# Teststand.net
KiCad netlist of a schematic drawn in EAGLE
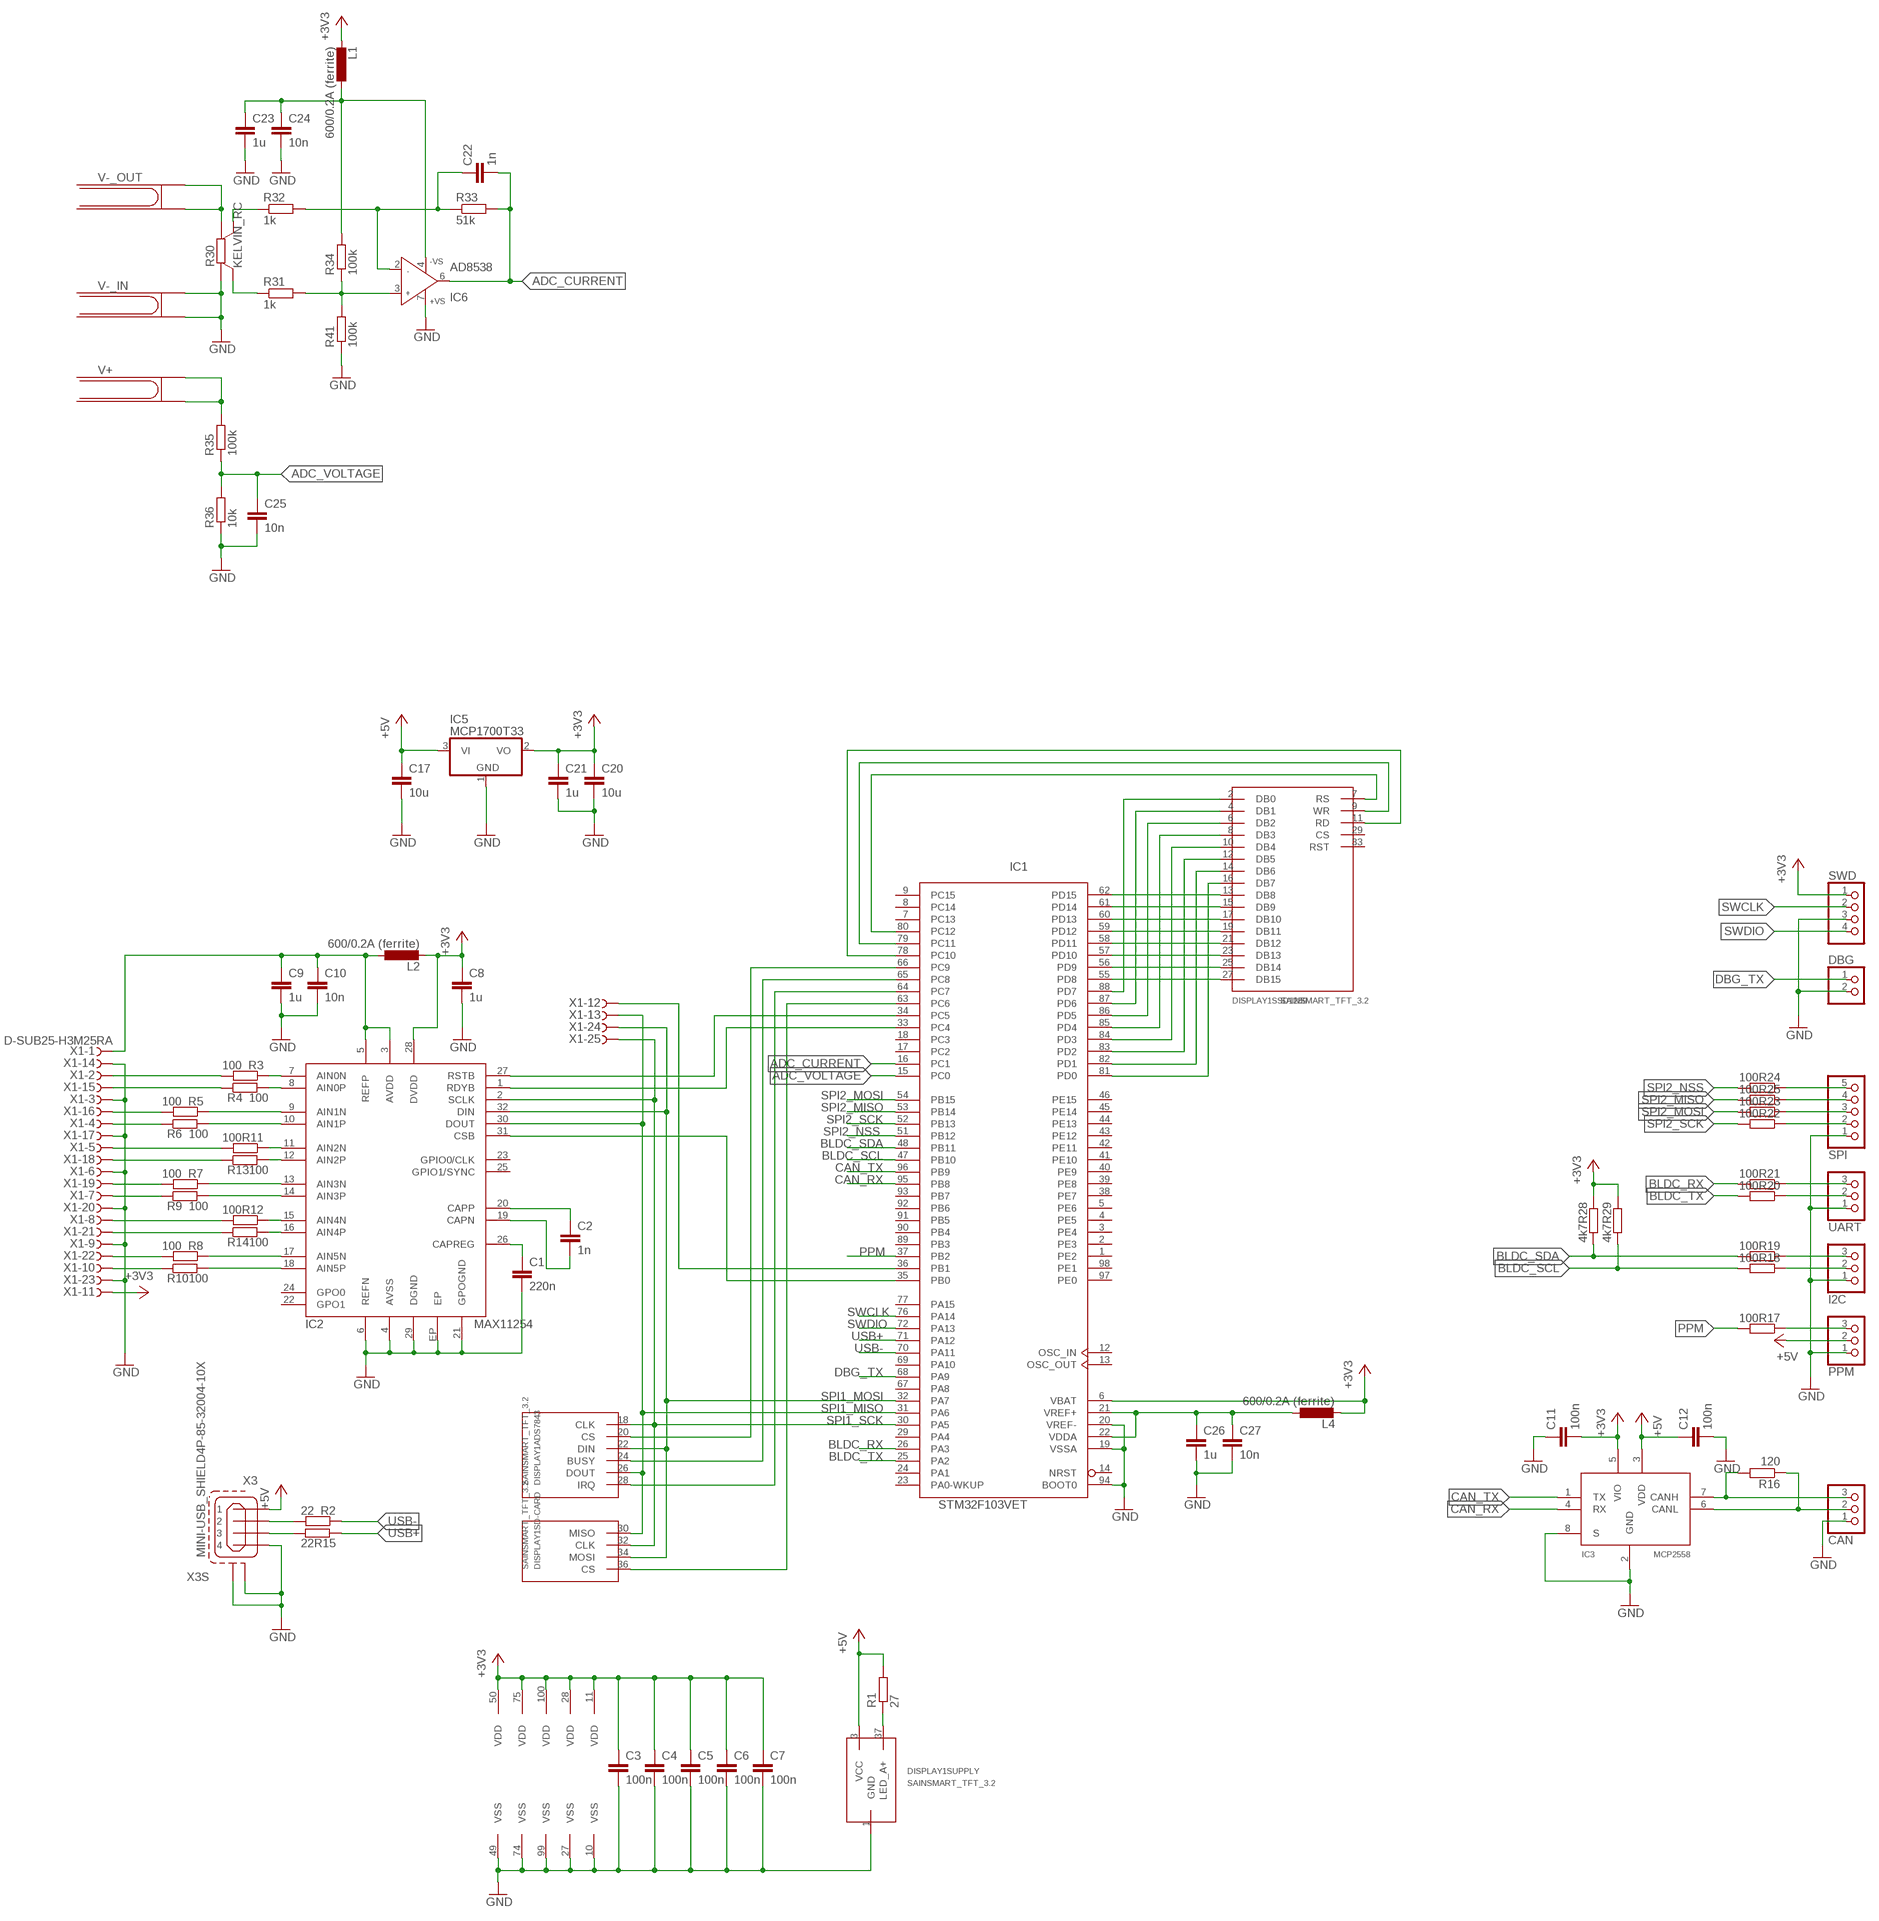
[diagram p0: schematic, sheet 1]

(export (version "E")
  (design (tool "Eeschema 10.0.6"))
  (components
    (comp (ref "C1")
      (value "220n")
      (footprint "eagle-import:C0603K")
      (libsource (lib "eagle-import") (part "C-EUC0603K"))
    )
    (comp (ref "C2")
      (value "1n")
      (footprint "eagle-import:C0603K")
      (libsource (lib "eagle-import") (part "C-EUC0603K"))
    )
    (comp (ref "C3")
      (value "100n")
      (footprint "eagle-import:C0603K")
      (libsource (lib "eagle-import") (part "C-EUC0603K"))
    )
    (comp (ref "C4")
      (value "100n")
      (footprint "eagle-import:C0603K")
      (libsource (lib "eagle-import") (part "C-EUC0603K"))
    )
    (comp (ref "C5")
      (value "100n")
      (footprint "eagle-import:C0603K")
      (libsource (lib "eagle-import") (part "C-EUC0603K"))
    )
    (comp (ref "C6")
      (value "100n")
      (footprint "eagle-import:C0603K")
      (libsource (lib "eagle-import") (part "C-EUC0603K"))
    )
    (comp (ref "C7")
      (value "100n")
      (footprint "eagle-import:C0603K")
      (libsource (lib "eagle-import") (part "C-EUC0603K"))
    )
    (comp (ref "C8")
      (value "1u")
      (footprint "eagle-import:C0603K")
      (libsource (lib "eagle-import") (part "C-EUC0603K"))
    )
    (comp (ref "C9")
      (value "1u")
      (footprint "eagle-import:C0603K")
      (libsource (lib "eagle-import") (part "C-EUC0603K"))
    )
    (comp (ref "C10")
      (value "10n")
      (footprint "eagle-import:C0603K")
      (libsource (lib "eagle-import") (part "C-EUC0603K"))
    )
    (comp (ref "C11")
      (value "100n")
      (footprint "eagle-import:C0603K")
      (libsource (lib "eagle-import") (part "C-EUC0603K"))
    )
    (comp (ref "C12")
      (value "100n")
      (footprint "eagle-import:C0603K")
      (libsource (lib "eagle-import") (part "C-EUC0603K"))
    )
    (comp (ref "C17")
      (value "10u")
      (footprint "eagle-import:C1206")
      (libsource (lib "eagle-import") (part "C-EUC1206"))
    )
    (comp (ref "C20")
      (value "10u")
      (footprint "eagle-import:C1206")
      (libsource (lib "eagle-import") (part "C-EUC1206"))
    )
    (comp (ref "C21")
      (value "1u")
      (footprint "eagle-import:C1206")
      (libsource (lib "eagle-import") (part "C-EUC1206"))
    )
    (comp (ref "C22")
      (value "1n")
      (footprint "eagle-import:C0603K")
      (libsource (lib "eagle-import") (part "C-EUC0603K"))
    )
    (comp (ref "C23")
      (value "1u")
      (footprint "eagle-import:C0603K")
      (libsource (lib "eagle-import") (part "C-EUC0603K"))
    )
    (comp (ref "C24")
      (value "10n")
      (footprint "eagle-import:C0603K")
      (libsource (lib "eagle-import") (part "C-EUC0603K"))
    )
    (comp (ref "C25")
      (value "10n")
      (footprint "eagle-import:C0603K")
      (libsource (lib "eagle-import") (part "C-EUC0603K"))
    )
    (comp (ref "C26")
      (value "1u")
      (footprint "eagle-import:C0603K")
      (libsource (lib "eagle-import") (part "C-EUC0603K"))
    )
    (comp (ref "C27")
      (value "10n")
      (footprint "eagle-import:C0603K")
      (libsource (lib "eagle-import") (part "C-EUC0603K"))
    )
    (comp (ref "CAN")
      (value "PINHD-1X3/90")
      (footprint "eagle-import:1X03_90")
      (libsource (lib "eagle-import") (part "PINHD-1X3/90"))
    )
    (comp (ref "DBG")
      (value "PINHD-1X2")
      (footprint "eagle-import:1X02")
      (libsource (lib "eagle-import") (part "PINHD-1X2"))
    )
    (comp (ref "DISPLAY1")
      (value "SAINSMART_TFT_3.2")
      (footprint "eagle-import:SAINSMART_TFT_3.2")
      (libsource (lib "eagle-import") (part "SAINSMART_TFT_3.2"))
    )
    (comp (ref "I2C")
      (value "PINHD-1X3/90")
      (footprint "eagle-import:1X03_90")
      (libsource (lib "eagle-import") (part "PINHD-1X3/90"))
    )
    (comp (ref "IC1")
      (value "STM32F103VET")
      (footprint "eagle-import:LQFP100")
      (libsource (lib "eagle-import") (part "STM32F103VTE"))
    )
    (comp (ref "IC2")
      (value "MAX11254")
      (footprint "eagle-import:TQFP32-EP")
      (libsource (lib "eagle-import") (part "MAX11254"))
    )
    (comp (ref "IC3")
      (value "MCP2558")
      (footprint "eagle-import:SOIC8")
      (libsource (lib "eagle-import") (part "MCP2558"))
    )
    (comp (ref "IC5")
      (value "MCP1700T33")
      (footprint "eagle-import:SOT23")
      (libsource (lib "eagle-import") (part "MCP1703CB"))
    )
    (comp (ref "IC6")
      (value "AD8538")
      (footprint "eagle-import:SO8")
      (fields (field (name "MPN") "AD8519ARZ"))
      (libsource (lib "eagle-import") (part "AD8519R"))
    )
    (comp (ref "L1")
      (value "600/0.2A (ferrite)")
      (footprint "eagle-import:L2012C")
      (libsource (lib "eagle-import") (part "L-EUL2012C"))
    )
    (comp (ref "L2")
      (value "600/0.2A (ferrite)")
      (footprint "eagle-import:L2012C")
      (libsource (lib "eagle-import") (part "L-EUL2012C"))
    )
    (comp (ref "L4")
      (value "600/0.2A (ferrite)")
      (footprint "eagle-import:L2012C")
      (libsource (lib "eagle-import") (part "L-EUL2012C"))
    )
    (comp (ref "PPM")
      (value "PINHD-1X3/90")
      (footprint "eagle-import:1X03_90")
      (libsource (lib "eagle-import") (part "PINHD-1X3/90"))
    )
    (comp (ref "R1")
      (value "27")
      (footprint "eagle-import:M1206")
      (libsource (lib "eagle-import") (part "R-EU_M1206"))
    )
    (comp (ref "R2")
      (value "22")
      (footprint "eagle-import:R0603")
      (libsource (lib "eagle-import") (part "R-EU_R0603"))
    )
    (comp (ref "R3")
      (value "100")
      (footprint "eagle-import:R0603")
      (libsource (lib "eagle-import") (part "R-EU_R0603"))
    )
    (comp (ref "R4")
      (value "100")
      (footprint "eagle-import:R0603")
      (libsource (lib "eagle-import") (part "R-EU_R0603"))
    )
    (comp (ref "R5")
      (value "100")
      (footprint "eagle-import:R0603")
      (libsource (lib "eagle-import") (part "R-EU_R0603"))
    )
    (comp (ref "R6")
      (value "100")
      (footprint "eagle-import:R0603")
      (libsource (lib "eagle-import") (part "R-EU_R0603"))
    )
    (comp (ref "R7")
      (value "100")
      (footprint "eagle-import:R0603")
      (libsource (lib "eagle-import") (part "R-EU_R0603"))
    )
    (comp (ref "R8")
      (value "100")
      (footprint "eagle-import:R0603")
      (libsource (lib "eagle-import") (part "R-EU_R0603"))
    )
    (comp (ref "R9")
      (value "100")
      (footprint "eagle-import:R0603")
      (libsource (lib "eagle-import") (part "R-EU_R0603"))
    )
    (comp (ref "R10")
      (value "100")
      (footprint "eagle-import:R0603")
      (libsource (lib "eagle-import") (part "R-EU_R0603"))
    )
    (comp (ref "R11")
      (value "100")
      (footprint "eagle-import:R0603")
      (libsource (lib "eagle-import") (part "R-EU_R0603"))
    )
    (comp (ref "R12")
      (value "100")
      (footprint "eagle-import:R0603")
      (libsource (lib "eagle-import") (part "R-EU_R0603"))
    )
    (comp (ref "R13")
      (value "100")
      (footprint "eagle-import:R0603")
      (libsource (lib "eagle-import") (part "R-EU_R0603"))
    )
    (comp (ref "R14")
      (value "100")
      (footprint "eagle-import:R0603")
      (libsource (lib "eagle-import") (part "R-EU_R0603"))
    )
    (comp (ref "R15")
      (value "22")
      (footprint "eagle-import:R0603")
      (libsource (lib "eagle-import") (part "R-EU_R0603"))
    )
    (comp (ref "R16")
      (value "120")
      (footprint "eagle-import:R0603")
      (libsource (lib "eagle-import") (part "R-EU_R0603"))
    )
    (comp (ref "R17")
      (value "100")
      (footprint "eagle-import:R0603")
      (libsource (lib "eagle-import") (part "R-EU_R0603"))
    )
    (comp (ref "R18")
      (value "100")
      (footprint "eagle-import:R0603")
      (libsource (lib "eagle-import") (part "R-EU_R0603"))
    )
    (comp (ref "R19")
      (value "100")
      (footprint "eagle-import:R0603")
      (libsource (lib "eagle-import") (part "R-EU_R0603"))
    )
    (comp (ref "R20")
      (value "100")
      (footprint "eagle-import:R0603")
      (libsource (lib "eagle-import") (part "R-EU_R0603"))
    )
    (comp (ref "R21")
      (value "100")
      (footprint "eagle-import:R0603")
      (libsource (lib "eagle-import") (part "R-EU_R0603"))
    )
    (comp (ref "R22")
      (value "100")
      (footprint "eagle-import:R0603")
      (libsource (lib "eagle-import") (part "R-EU_R0603"))
    )
    (comp (ref "R23")
      (value "100")
      (footprint "eagle-import:R0603")
      (libsource (lib "eagle-import") (part "R-EU_R0603"))
    )
    (comp (ref "R24")
      (value "100")
      (footprint "eagle-import:R0603")
      (libsource (lib "eagle-import") (part "R-EU_R0603"))
    )
    (comp (ref "R25")
      (value "100")
      (footprint "eagle-import:R0603")
      (libsource (lib "eagle-import") (part "R-EU_R0603"))
    )
    (comp (ref "R28")
      (value "4k7")
      (footprint "eagle-import:R0603")
      (libsource (lib "eagle-import") (part "R-EU_R0603"))
    )
    (comp (ref "R29")
      (value "4k7")
      (footprint "eagle-import:R0603")
      (libsource (lib "eagle-import") (part "R-EU_R0603"))
    )
    (comp (ref "R30")
      (value "KELVIN_RC")
      (footprint "eagle-import:CST0612")
      (libsource (lib "eagle-import") (part "KELVIN_RC"))
    )
    (comp (ref "R31")
      (value "1k")
      (footprint "eagle-import:R0603")
      (libsource (lib "eagle-import") (part "R-EU_R0603"))
    )
    (comp (ref "R32")
      (value "1k")
      (footprint "eagle-import:R0603")
      (libsource (lib "eagle-import") (part "R-EU_R0603"))
    )
    (comp (ref "R33")
      (value "51k")
      (footprint "eagle-import:R0603")
      (libsource (lib "eagle-import") (part "R-EU_R0603"))
    )
    (comp (ref "R34")
      (value "100k")
      (footprint "eagle-import:R0603")
      (libsource (lib "eagle-import") (part "R-EU_R0603"))
    )
    (comp (ref "R35")
      (value "100k")
      (footprint "eagle-import:R0603")
      (libsource (lib "eagle-import") (part "R-EU_R0603"))
    )
    (comp (ref "R36")
      (value "10k")
      (footprint "eagle-import:R0603")
      (libsource (lib "eagle-import") (part "R-EU_R0603"))
    )
    (comp (ref "R41")
      (value "100k")
      (footprint "eagle-import:R0603")
      (libsource (lib "eagle-import") (part "R-EU_R0603"))
    )
    (comp (ref "SPI")
      (value "PINHD-1X5/90")
      (footprint "eagle-import:1X05_90")
      (libsource (lib "eagle-import") (part "PINHD-1X5/90"))
    )
    (comp (ref "SWD")
      (value "PINHD-1X4")
      (footprint "eagle-import:1X04")
      (libsource (lib "eagle-import") (part "PINHD-1X4"))
    )
    (comp (ref "UART")
      (value "PINHD-1X3/90")
      (footprint "eagle-import:1X03_90")
      (libsource (lib "eagle-import") (part "PINHD-1X3/90"))
    )
    (comp (ref "V+")
      (value "4MMJACK")
      (footprint "eagle-import:4MMJACK")
      (libsource (lib "eagle-import") (part "4MMJACK"))
    )
    (comp (ref "V-_IN")
      (value "4MMJACK")
      (footprint "eagle-import:4MMJACK")
      (libsource (lib "eagle-import") (part "4MMJACK"))
    )
    (comp (ref "V-_OUT")
      (value "4MMJACK")
      (footprint "eagle-import:4MMJACK")
      (libsource (lib "eagle-import") (part "4MMJACK"))
    )
    (comp (ref "X1")
      (value "D-SUB25-H3M25RA")
      (footprint "eagle-import:H3M25RA")
      (libsource (lib "eagle-import") (part "D-SUB25-H3M25RA"))
    )
    (comp (ref "X3")
      (value "MINI-USB_SHIELD4P-85-32004-10X")
      (footprint "eagle-import:85-32004-10X")
      (libsource (lib "eagle-import") (part "MINI-USB_SHIELD4P-85-32004-10X"))
    )
  )
  (nets
    (net (code "1") (name "+3V3") (class "Default")
      (node (ref "C11") (pin "2") (pinfunction "2_2") (pintype "passive"))
      (node (ref "C20") (pin "1") (pinfunction "1_1") (pintype "passive"))
      (node (ref "C21") (pin "1") (pinfunction "1_1") (pintype "passive"))
      (node (ref "C3") (pin "1") (pinfunction "1_1") (pintype "passive"))
      (node (ref "C4") (pin "1") (pinfunction "1_1") (pintype "passive"))
      (node (ref "C5") (pin "1") (pinfunction "1_1") (pintype "passive"))
      (node (ref "C6") (pin "1") (pinfunction "1_1") (pintype "passive"))
      (node (ref "C7") (pin "1") (pinfunction "1_1") (pintype "passive"))
      (node (ref "C8") (pin "1") (pinfunction "1_1") (pintype "passive"))
      (node (ref "IC1") (pin "100") (pinfunction "VDD_100") (pintype "power_in"))
      (node (ref "IC1") (pin "11") (pinfunction "VDD_11") (pintype "power_in"))
      (node (ref "IC1") (pin "28") (pinfunction "VDD_28") (pintype "power_in"))
      (node (ref "IC1") (pin "50") (pinfunction "VDD_50") (pintype "power_in"))
      (node (ref "IC1") (pin "6") (pinfunction "VBAT_6") (pintype "power_in"))
      (node (ref "IC1") (pin "75") (pinfunction "VDD_75") (pintype "power_in"))
      (node (ref "IC2") (pin "28") (pinfunction "DVDD_28") (pintype "bidirectional"))
      (node (ref "IC3") (pin "5") (pinfunction "VIO_5") (pintype "bidirectional"))
      (node (ref "IC5") (pin "2") (pinfunction "VO_2") (pintype "passive"))
      (node (ref "L1") (pin "2") (pinfunction "2_2") (pintype "passive"))
      (node (ref "L2") (pin "2") (pinfunction "2_2") (pintype "passive"))
      (node (ref "L4") (pin "2") (pinfunction "2_2") (pintype "passive"))
      (node (ref "R28") (pin "1") (pinfunction "1_1") (pintype "passive"))
      (node (ref "R29") (pin "1") (pinfunction "1_1") (pintype "passive"))
      (node (ref "SWD") (pin "1") (pinfunction "1_1") (pintype "passive"))
      (node (ref "X1") (pin "11") (pinfunction "F_11") (pintype "passive"))
    )
    (net (code "2") (name "+5V") (class "Default")
      (node (ref "C12") (pin "1") (pinfunction "1_1") (pintype "passive"))
      (node (ref "C17") (pin "1") (pinfunction "1_1") (pintype "passive"))
      (node (ref "DISPLAY1") (pin "3") (pinfunction "VCC_3") (pintype "bidirectional"))
      (node (ref "IC3") (pin "3") (pinfunction "VDD_3") (pintype "bidirectional"))
      (node (ref "IC5") (pin "3") (pinfunction "VI_3") (pintype "input"))
      (node (ref "PPM") (pin "2") (pinfunction "2_2") (pintype "passive"))
      (node (ref "R1") (pin "2") (pinfunction "2_2") (pintype "passive"))
      (node (ref "X3") (pin "1") (pinfunction "1_1") (pintype "passive"))
    )
    (net (code "3") (name "/SPI1_MISO") (class "Default")
      (node (ref "DISPLAY1") (pin "26") (pinfunction "DOUT_26") (pintype "bidirectional"))
      (node (ref "DISPLAY1") (pin "30") (pinfunction "MISO_30") (pintype "bidirectional"))
      (node (ref "IC1") (pin "31") (pinfunction "PA6_31") (pintype "bidirectional"))
      (node (ref "IC2") (pin "30") (pinfunction "DOUT_30") (pintype "bidirectional"))
      (node (ref "X1") (pin "13") (pinfunction "F_13") (pintype "passive"))
    )
    (net (code "4") (name "/SPI1_MOSI") (class "Default")
      (node (ref "DISPLAY1") (pin "22") (pinfunction "DIN_22") (pintype "bidirectional"))
      (node (ref "DISPLAY1") (pin "34") (pinfunction "MOSI_34") (pintype "bidirectional"))
      (node (ref "IC1") (pin "32") (pinfunction "PA7_32") (pintype "bidirectional"))
      (node (ref "IC2") (pin "32") (pinfunction "DIN_32") (pintype "bidirectional"))
      (node (ref "X1") (pin "24") (pinfunction "F_24") (pintype "passive"))
    )
    (net (code "5") (name "/SPI1_SCK") (class "Default")
      (node (ref "DISPLAY1") (pin "18") (pinfunction "CLK_18") (pintype "bidirectional"))
      (node (ref "DISPLAY1") (pin "32") (pinfunction "CLK_32") (pintype "bidirectional"))
      (node (ref "IC1") (pin "30") (pinfunction "PA5_30") (pintype "bidirectional"))
      (node (ref "IC2") (pin "2") (pinfunction "SCLK_2") (pintype "bidirectional"))
      (node (ref "X1") (pin "25") (pinfunction "F_25") (pintype "passive"))
    )
    (net (code "6") (name "ADC_CURRENT") (class "Default")
      (node (ref "C22") (pin "2") (pinfunction "2_2") (pintype "passive"))
      (node (ref "IC1") (pin "16") (pinfunction "PC1_16") (pintype "bidirectional"))
      (node (ref "IC6") (pin "6") (pinfunction "OUT_6") (pintype "output"))
      (node (ref "R33") (pin "2") (pinfunction "2_2") (pintype "passive"))
    )
    (net (code "7") (name "ADC_VOLTAGE") (class "Default")
      (node (ref "C25") (pin "1") (pinfunction "1_1") (pintype "passive"))
      (node (ref "IC1") (pin "15") (pinfunction "PC0_15") (pintype "bidirectional"))
      (node (ref "R35") (pin "1") (pinfunction "1_1") (pintype "passive"))
      (node (ref "R36") (pin "2") (pinfunction "2_2") (pintype "passive"))
    )
    (net (code "8") (name "BLDC_RX") (class "Default")
      (node (ref "IC1") (pin "26") (pinfunction "PA3_26") (pintype "bidirectional"))
      (node (ref "R21") (pin "2") (pinfunction "2_2") (pintype "passive"))
    )
    (net (code "9") (name "BLDC_SCL") (class "Default")
      (node (ref "IC1") (pin "47") (pinfunction "PB10_47") (pintype "bidirectional"))
      (node (ref "R18") (pin "2") (pinfunction "2_2") (pintype "passive"))
      (node (ref "R29") (pin "2") (pinfunction "2_2") (pintype "passive"))
    )
    (net (code "10") (name "BLDC_SDA") (class "Default")
      (node (ref "IC1") (pin "48") (pinfunction "PB11_48") (pintype "bidirectional"))
      (node (ref "R19") (pin "2") (pinfunction "2_2") (pintype "passive"))
      (node (ref "R28") (pin "2") (pinfunction "2_2") (pintype "passive"))
    )
    (net (code "11") (name "BLDC_TX") (class "Default")
      (node (ref "IC1") (pin "25") (pinfunction "PA2_25") (pintype "bidirectional"))
      (node (ref "R20") (pin "2") (pinfunction "2_2") (pintype "passive"))
    )
    (net (code "12") (name "CAN_RX") (class "Default")
      (node (ref "IC1") (pin "95") (pinfunction "PB8_95") (pintype "bidirectional"))
      (node (ref "IC3") (pin "4") (pinfunction "RX_4") (pintype "bidirectional"))
    )
    (net (code "13") (name "CAN_TX") (class "Default")
      (node (ref "IC1") (pin "96") (pinfunction "PB9_96") (pintype "bidirectional"))
      (node (ref "IC3") (pin "1") (pinfunction "TX_1") (pintype "bidirectional"))
    )
    (net (code "14") (name "DBG_TX") (class "Default")
      (node (ref "DBG") (pin "1") (pinfunction "1_1") (pintype "passive"))
      (node (ref "IC1") (pin "68") (pinfunction "PA9_68") (pintype "bidirectional"))
    )
    (net (code "15") (name "GND") (class "Default")
      (node (ref "C1") (pin "2") (pinfunction "2_2") (pintype "passive"))
      (node (ref "C10") (pin "2") (pinfunction "2_2") (pintype "passive"))
      (node (ref "C11") (pin "1") (pinfunction "1_1") (pintype "passive"))
      (node (ref "C12") (pin "2") (pinfunction "2_2") (pintype "passive"))
      (node (ref "C17") (pin "2") (pinfunction "2_2") (pintype "passive"))
      (node (ref "C20") (pin "2") (pinfunction "2_2") (pintype "passive"))
      (node (ref "C21") (pin "2") (pinfunction "2_2") (pintype "passive"))
      (node (ref "C23") (pin "2") (pinfunction "2_2") (pintype "passive"))
      (node (ref "C24") (pin "2") (pinfunction "2_2") (pintype "passive"))
      (node (ref "C25") (pin "2") (pinfunction "2_2") (pintype "passive"))
      (node (ref "C26") (pin "2") (pinfunction "2_2") (pintype "passive"))
      (node (ref "C27") (pin "2") (pinfunction "2_2") (pintype "passive"))
      (node (ref "C3") (pin "2") (pinfunction "2_2") (pintype "passive"))
      (node (ref "C4") (pin "2") (pinfunction "2_2") (pintype "passive"))
      (node (ref "C5") (pin "2") (pinfunction "2_2") (pintype "passive"))
      (node (ref "C6") (pin "2") (pinfunction "2_2") (pintype "passive"))
      (node (ref "C7") (pin "2") (pinfunction "2_2") (pintype "passive"))
      (node (ref "C8") (pin "2") (pinfunction "2_2") (pintype "passive"))
      (node (ref "C9") (pin "2") (pinfunction "2_2") (pintype "passive"))
      (node (ref "CAN") (pin "1") (pinfunction "1_1") (pintype "passive"))
      (node (ref "DBG") (pin "2") (pinfunction "2_2") (pintype "passive"))
      (node (ref "DISPLAY1") (pin "1") (pinfunction "GND_1") (pintype "bidirectional"))
      (node (ref "I2C") (pin "1") (pinfunction "1_1") (pintype "passive"))
      (node (ref "IC1") (pin "10") (pinfunction "VSS_10") (pintype "power_in"))
      (node (ref "IC1") (pin "19") (pinfunction "VSSA_19") (pintype "power_in"))
      (node (ref "IC1") (pin "20") (pinfunction "VREF-_20") (pintype "power_in"))
      (node (ref "IC1") (pin "27") (pinfunction "VSS_27") (pintype "power_in"))
      (node (ref "IC1") (pin "49") (pinfunction "VSS_49") (pintype "power_in"))
      (node (ref "IC1") (pin "74") (pinfunction "VSS_74") (pintype "power_in"))
      (node (ref "IC1") (pin "94") (pinfunction "BOOT0_94") (pintype "input"))
      (node (ref "IC1") (pin "99") (pinfunction "VSS_99") (pintype "power_in"))
      (node (ref "IC2") (pin "21") (pinfunction "GPOGND_21") (pintype "bidirectional"))
      (node (ref "IC2") (pin "29") (pinfunction "DGND_29") (pintype "bidirectional"))
      (node (ref "IC2") (pin "4") (pinfunction "AVSS_4") (pintype "bidirectional"))
      (node (ref "IC2") (pin "6") (pinfunction "REFN_6") (pintype "bidirectional"))
      (node (ref "IC2") (pin "EP") (pinfunction "EP_EP") (pintype "bidirectional"))
      (node (ref "IC3") (pin "2") (pinfunction "GND_2") (pintype "bidirectional"))
      (node (ref "IC3") (pin "8") (pinfunction "S_8") (pintype "bidirectional"))
      (node (ref "IC5") (pin "1") (pinfunction "GND_1") (pintype "passive"))
      (node (ref "IC6") (pin "7") (pinfunction "+VS_7") (pintype "input"))
      (node (ref "PPM") (pin "1") (pinfunction "1_1") (pintype "passive"))
      (node (ref "R30") (pin "B") (pinfunction "B_B") (pintype "passive"))
      (node (ref "R36") (pin "1") (pinfunction "1_1") (pintype "passive"))
      (node (ref "R41") (pin "1") (pinfunction "1_1") (pintype "passive"))
      (node (ref "SPI") (pin "1") (pinfunction "1_1") (pintype "passive"))
      (node (ref "SWD") (pin "3") (pinfunction "3_3") (pintype "passive"))
      (node (ref "UART") (pin "1") (pinfunction "1_1") (pintype "passive"))
      (node (ref "V-_IN") (pin "1@1") (pinfunction "1_1@1") (pintype "bidirectional"))
      (node (ref "V-_IN") (pin "1@2") (pinfunction "2_1@2") (pintype "bidirectional"))
      (node (ref "X1") (pin "14") (pinfunction "F_14") (pintype "passive"))
      (node (ref "X1") (pin "17") (pinfunction "F_17") (pintype "passive"))
      (node (ref "X1") (pin "20") (pinfunction "F_20") (pintype "passive"))
      (node (ref "X1") (pin "23") (pinfunction "F_23") (pintype "passive"))
      (node (ref "X1") (pin "3") (pinfunction "F_3") (pintype "passive"))
      (node (ref "X1") (pin "6") (pinfunction "F_6") (pintype "passive"))
      (node (ref "X1") (pin "9") (pinfunction "F_9") (pintype "passive"))
      (node (ref "X3") (pin "4") (pinfunction "4_4") (pintype "passive"))
      (node (ref "X3") (pin "M1") (pinfunction "S1_M1") (pintype "passive"))
      (node (ref "X3") (pin "M2") (pinfunction "S2_M2") (pintype "passive"))
    )
    (net (code "16") (name "Net-(DISPLAY1A-BUSY)") (class "Default")
      (node (ref "DISPLAY1") (pin "24") (pinfunction "BUSY_24") (pintype "bidirectional"))
      (node (ref "IC1") (pin "65") (pinfunction "PC8_65") (pintype "bidirectional"))
    )
    (net (code "17") (name "Net-(DISPLAY1A-CS)") (class "Default")
      (node (ref "DISPLAY1") (pin "20") (pinfunction "CS_20") (pintype "bidirectional"))
      (node (ref "IC1") (pin "66") (pinfunction "PC9_66") (pintype "bidirectional"))
    )
    (net (code "18") (name "Net-(DISPLAY1A-IRQ)") (class "Default")
      (node (ref "DISPLAY1") (pin "28") (pinfunction "IRQ_28") (pintype "bidirectional"))
      (node (ref "IC1") (pin "64") (pinfunction "PC7_64") (pintype "bidirectional"))
    )
    (net (code "19") (name "Net-(DISPLAY1B-CS)") (class "Default")
      (node (ref "DISPLAY1") (pin "36") (pinfunction "CS_36") (pintype "bidirectional"))
      (node (ref "IC1") (pin "63") (pinfunction "PC6_63") (pintype "bidirectional"))
    )
    (net (code "20") (name "Net-(DISPLAY1C-DB0)") (class "Default")
      (node (ref "DISPLAY1") (pin "2") (pinfunction "DB0_2") (pintype "bidirectional"))
      (node (ref "IC1") (pin "88") (pinfunction "PD7_88") (pintype "bidirectional"))
    )
    (net (code "21") (name "Net-(DISPLAY1C-DB1)") (class "Default")
      (node (ref "DISPLAY1") (pin "4") (pinfunction "DB1_4") (pintype "bidirectional"))
      (node (ref "IC1") (pin "87") (pinfunction "PD6_87") (pintype "bidirectional"))
    )
    (net (code "22") (name "Net-(DISPLAY1C-DB2)") (class "Default")
      (node (ref "DISPLAY1") (pin "6") (pinfunction "DB2_6") (pintype "bidirectional"))
      (node (ref "IC1") (pin "86") (pinfunction "PD5_86") (pintype "bidirectional"))
    )
    (net (code "23") (name "Net-(DISPLAY1C-DB3)") (class "Default")
      (node (ref "DISPLAY1") (pin "8") (pinfunction "DB3_8") (pintype "bidirectional"))
      (node (ref "IC1") (pin "85") (pinfunction "PD4_85") (pintype "bidirectional"))
    )
    (net (code "24") (name "Net-(DISPLAY1C-DB4)") (class "Default")
      (node (ref "DISPLAY1") (pin "10") (pinfunction "DB4_10") (pintype "bidirectional"))
      (node (ref "IC1") (pin "84") (pinfunction "PD3_84") (pintype "bidirectional"))
    )
    (net (code "25") (name "Net-(DISPLAY1C-DB5)") (class "Default")
      (node (ref "DISPLAY1") (pin "12") (pinfunction "DB5_12") (pintype "bidirectional"))
      (node (ref "IC1") (pin "83") (pinfunction "PD2_83") (pintype "bidirectional"))
    )
    (net (code "26") (name "Net-(DISPLAY1C-DB6)") (class "Default")
      (node (ref "DISPLAY1") (pin "14") (pinfunction "DB6_14") (pintype "bidirectional"))
      (node (ref "IC1") (pin "82") (pinfunction "PD1_82") (pintype "bidirectional"))
    )
    (net (code "27") (name "Net-(DISPLAY1C-DB7)") (class "Default")
      (node (ref "DISPLAY1") (pin "16") (pinfunction "DB7_16") (pintype "bidirectional"))
      (node (ref "IC1") (pin "81") (pinfunction "PD0_81") (pintype "bidirectional"))
    )
    (net (code "28") (name "Net-(DISPLAY1C-DB8)") (class "Default")
      (node (ref "DISPLAY1") (pin "13") (pinfunction "DB8_13") (pintype "bidirectional"))
      (node (ref "IC1") (pin "62") (pinfunction "PD15_62") (pintype "bidirectional"))
    )
    (net (code "29") (name "Net-(DISPLAY1C-DB9)") (class "Default")
      (node (ref "DISPLAY1") (pin "15") (pinfunction "DB9_15") (pintype "bidirectional"))
      (node (ref "IC1") (pin "61") (pinfunction "PD14_61") (pintype "bidirectional"))
    )
    (net (code "30") (name "Net-(DISPLAY1C-DB10)") (class "Default")
      (node (ref "DISPLAY1") (pin "17") (pinfunction "DB10_17") (pintype "bidirectional"))
      (node (ref "IC1") (pin "60") (pinfunction "PD13_60") (pintype "bidirectional"))
    )
    (net (code "31") (name "Net-(DISPLAY1C-DB11)") (class "Default")
      (node (ref "DISPLAY1") (pin "19") (pinfunction "DB11_19") (pintype "bidirectional"))
      (node (ref "IC1") (pin "59") (pinfunction "PD12_59") (pintype "bidirectional"))
    )
    (net (code "32") (name "Net-(DISPLAY1C-DB12)") (class "Default")
      (node (ref "DISPLAY1") (pin "21") (pinfunction "DB12_21") (pintype "bidirectional"))
      (node (ref "IC1") (pin "58") (pinfunction "PD11_58") (pintype "bidirectional"))
    )
    (net (code "33") (name "Net-(DISPLAY1C-DB13)") (class "Default")
      (node (ref "DISPLAY1") (pin "23") (pinfunction "DB13_23") (pintype "bidirectional"))
      (node (ref "IC1") (pin "57") (pinfunction "PD10_57") (pintype "bidirectional"))
    )
    (net (code "34") (name "Net-(DISPLAY1C-DB14)") (class "Default")
      (node (ref "DISPLAY1") (pin "25") (pinfunction "DB14_25") (pintype "bidirectional"))
      (node (ref "IC1") (pin "56") (pinfunction "PD9_56") (pintype "bidirectional"))
    )
    (net (code "35") (name "Net-(DISPLAY1C-DB15)") (class "Default")
      (node (ref "DISPLAY1") (pin "27") (pinfunction "DB15_27") (pintype "bidirectional"))
      (node (ref "IC1") (pin "55") (pinfunction "PD8_55") (pintype "bidirectional"))
    )
    (net (code "36") (name "Net-(DISPLAY1C-RD)") (class "Default")
      (node (ref "DISPLAY1") (pin "11") (pinfunction "RD_11") (pintype "bidirectional"))
      (node (ref "IC1") (pin "78") (pinfunction "PC10_78") (pintype "bidirectional"))
    )
    (net (code "37") (name "Net-(DISPLAY1C-RS)") (class "Default")
      (node (ref "DISPLAY1") (pin "7") (pinfunction "RS_7") (pintype "bidirectional"))
      (node (ref "IC1") (pin "80") (pinfunction "PC12_80") (pintype "bidirectional"))
    )
    (net (code "38") (name "Net-(DISPLAY1C-WR)") (class "Default")
      (node (ref "DISPLAY1") (pin "9") (pinfunction "WR_9") (pintype "bidirectional"))
      (node (ref "IC1") (pin "79") (pinfunction "PC11_79") (pintype "bidirectional"))
    )
    (net (code "39") (name "Net-(DISPLAY1D-LED_A+)") (class "Default")
      (node (ref "DISPLAY1") (pin "37") (pinfunction "LED_A+_37") (pintype "bidirectional"))
      (node (ref "R1") (pin "1") (pinfunction "1_1") (pintype "passive"))
    )
    (net (code "40") (name "Net-(I2C-Pad2)") (class "Default")
      (node (ref "I2C") (pin "2") (pinfunction "2_2") (pintype "passive"))
      (node (ref "R18") (pin "1") (pinfunction "1_1") (pintype "passive"))
    )
    (net (code "41") (name "Net-(I2C-Pad3)") (class "Default")
      (node (ref "I2C") (pin "3") (pinfunction "3_3") (pintype "passive"))
      (node (ref "R19") (pin "1") (pinfunction "1_1") (pintype "passive"))
    )
    (net (code "42") (name "Net-(IC1A-PB0)") (class "Default")
      (node (ref "IC1") (pin "35") (pinfunction "PB0_35") (pintype "bidirectional"))
      (node (ref "IC2") (pin "31") (pinfunction "CSB_31") (pintype "bidirectional"))
    )
    (net (code "43") (name "Net-(IC1A-PB1)") (class "Default")
      (node (ref "IC1") (pin "36") (pinfunction "PB1_36") (pintype "bidirectional"))
      (node (ref "X1") (pin "12") (pinfunction "F_12") (pintype "passive"))
    )
    (net (code "44") (name "Net-(IC1A-PC4)") (class "Default")
      (node (ref "IC1") (pin "33") (pinfunction "PC4_33") (pintype "bidirectional"))
      (node (ref "IC2") (pin "1") (pinfunction "RDYB_1") (pintype "bidirectional"))
    )
    (net (code "45") (name "Net-(IC1A-PC5)") (class "Default")
      (node (ref "IC1") (pin "34") (pinfunction "PC5_34") (pintype "bidirectional"))
      (node (ref "IC2") (pin "27") (pinfunction "RSTB_27") (pintype "bidirectional"))
    )
    (net (code "46") (name "Net-(IC1A-VDDA)") (class "Default")
      (node (ref "C26") (pin "1") (pinfunction "1_1") (pintype "passive"))
      (node (ref "C27") (pin "1") (pinfunction "1_1") (pintype "passive"))
      (node (ref "IC1") (pin "21") (pinfunction "VREF+_21") (pintype "power_in"))
      (node (ref "IC1") (pin "22") (pinfunction "VDDA_22") (pintype "power_in"))
      (node (ref "L4") (pin "1") (pinfunction "1_1") (pintype "passive"))
    )
    (net (code "47") (name "Net-(IC2-AIN0N)") (class "Default")
      (node (ref "IC2") (pin "7") (pinfunction "AIN0N_7") (pintype "bidirectional"))
      (node (ref "R3") (pin "1") (pinfunction "1_1") (pintype "passive"))
    )
    (net (code "48") (name "Net-(IC2-AIN0P)") (class "Default")
      (node (ref "IC2") (pin "8") (pinfunction "AIN0P_8") (pintype "bidirectional"))
      (node (ref "R4") (pin "2") (pinfunction "2_2") (pintype "passive"))
    )
    (net (code "49") (name "Net-(IC2-AIN1N)") (class "Default")
      (node (ref "IC2") (pin "9") (pinfunction "AIN1N_9") (pintype "bidirectional"))
      (node (ref "R5") (pin "1") (pinfunction "1_1") (pintype "passive"))
    )
    (net (code "50") (name "Net-(IC2-AIN1P)") (class "Default")
      (node (ref "IC2") (pin "10") (pinfunction "AIN1P_10") (pintype "bidirectional"))
      (node (ref "R6") (pin "2") (pinfunction "2_2") (pintype "passive"))
    )
    (net (code "51") (name "Net-(IC2-AIN2N)") (class "Default")
      (node (ref "IC2") (pin "11") (pinfunction "AIN2N_11") (pintype "bidirectional"))
      (node (ref "R11") (pin "1") (pinfunction "1_1") (pintype "passive"))
    )
    (net (code "52") (name "Net-(IC2-AIN2P)") (class "Default")
      (node (ref "IC2") (pin "12") (pinfunction "AIN2P_12") (pintype "bidirectional"))
      (node (ref "R13") (pin "2") (pinfunction "2_2") (pintype "passive"))
    )
    (net (code "53") (name "Net-(IC2-AIN3N)") (class "Default")
      (node (ref "IC2") (pin "13") (pinfunction "AIN3N_13") (pintype "bidirectional"))
      (node (ref "R7") (pin "1") (pinfunction "1_1") (pintype "passive"))
    )
    (net (code "54") (name "Net-(IC2-AIN3P)") (class "Default")
      (node (ref "IC2") (pin "14") (pinfunction "AIN3P_14") (pintype "bidirectional"))
      (node (ref "R9") (pin "2") (pinfunction "2_2") (pintype "passive"))
    )
    (net (code "55") (name "Net-(IC2-AIN4N)") (class "Default")
      (node (ref "IC2") (pin "15") (pinfunction "AIN4N_15") (pintype "bidirectional"))
      (node (ref "R12") (pin "1") (pinfunction "1_1") (pintype "passive"))
    )
    (net (code "56") (name "Net-(IC2-AIN4P)") (class "Default")
      (node (ref "IC2") (pin "16") (pinfunction "AIN4P_16") (pintype "bidirectional"))
      (node (ref "R14") (pin "2") (pinfunction "2_2") (pintype "passive"))
    )
    (net (code "57") (name "Net-(IC2-AIN5N)") (class "Default")
      (node (ref "IC2") (pin "17") (pinfunction "AIN5N_17") (pintype "bidirectional"))
      (node (ref "R8") (pin "1") (pinfunction "1_1") (pintype "passive"))
    )
    (net (code "58") (name "Net-(IC2-AIN5P)") (class "Default")
      (node (ref "IC2") (pin "18") (pinfunction "AIN5P_18") (pintype "bidirectional"))
      (node (ref "R10") (pin "2") (pinfunction "2_2") (pintype "passive"))
    )
    (net (code "59") (name "Net-(IC2-AVDD)") (class "Default")
      (node (ref "C10") (pin "1") (pinfunction "1_1") (pintype "passive"))
      (node (ref "C9") (pin "1") (pinfunction "1_1") (pintype "passive"))
      (node (ref "IC2") (pin "3") (pinfunction "AVDD_3") (pintype "bidirectional"))
      (node (ref "IC2") (pin "5") (pinfunction "REFP_5") (pintype "bidirectional"))
      (node (ref "L2") (pin "1") (pinfunction "1_1") (pintype "passive"))
      (node (ref "X1") (pin "1") (pinfunction "F_1") (pintype "passive"))
    )
    (net (code "60") (name "Net-(IC2-CAPN)") (class "Default")
      (node (ref "C2") (pin "2") (pinfunction "2_2") (pintype "passive"))
      (node (ref "IC2") (pin "19") (pinfunction "CAPN_19") (pintype "bidirectional"))
    )
    (net (code "61") (name "Net-(IC2-CAPP)") (class "Default")
      (node (ref "C2") (pin "1") (pinfunction "1_1") (pintype "passive"))
      (node (ref "IC2") (pin "20") (pinfunction "CAPP_20") (pintype "bidirectional"))
    )
    (net (code "62") (name "Net-(IC2-CAPREG)") (class "Default")
      (node (ref "C1") (pin "1") (pinfunction "1_1") (pintype "passive"))
      (node (ref "IC2") (pin "26") (pinfunction "CAPREG_26") (pintype "bidirectional"))
    )
    (net (code "63") (name "Net-(IC3-CANH)") (class "Default")
      (node (ref "CAN") (pin "3") (pinfunction "3_3") (pintype "passive"))
      (node (ref "IC3") (pin "7") (pinfunction "CANH_7") (pintype "bidirectional"))
      (node (ref "R16") (pin "2") (pinfunction "2_2") (pintype "passive"))
    )
    (net (code "64") (name "Net-(IC3-CANL)") (class "Default")
      (node (ref "CAN") (pin "2") (pinfunction "2_2") (pintype "passive"))
      (node (ref "IC3") (pin "6") (pinfunction "CANL_6") (pintype "bidirectional"))
      (node (ref "R16") (pin "1") (pinfunction "1_1") (pintype "passive"))
    )
    (net (code "65") (name "Net-(IC6--VS)") (class "Default")
      (node (ref "C23") (pin "1") (pinfunction "1_1") (pintype "passive"))
      (node (ref "C24") (pin "1") (pinfunction "1_1") (pintype "passive"))
      (node (ref "IC6") (pin "4") (pinfunction "-VS_4") (pintype "input"))
      (node (ref "L1") (pin "1") (pinfunction "1_1") (pintype "passive"))
      (node (ref "R34") (pin "2") (pinfunction "2_2") (pintype "passive"))
    )
    (net (code "66") (name "Net-(IC6-IN+)") (class "Default")
      (node (ref "IC6") (pin "3") (pinfunction "IN+_3") (pintype "input"))
      (node (ref "R31") (pin "2") (pinfunction "2_2") (pintype "passive"))
      (node (ref "R34") (pin "1") (pinfunction "1_1") (pintype "passive"))
      (node (ref "R41") (pin "2") (pinfunction "2_2") (pintype "passive"))
    )
    (net (code "67") (name "Net-(IC6-IN-)") (class "Default")
      (node (ref "C22") (pin "1") (pinfunction "1_1") (pintype "passive"))
      (node (ref "IC6") (pin "2") (pinfunction "IN-_2") (pintype "input"))
      (node (ref "R32") (pin "2") (pinfunction "2_2") (pintype "passive"))
      (node (ref "R33") (pin "1") (pinfunction "1_1") (pintype "passive"))
    )
    (net (code "68") (name "Net-(PPM-Pad3)") (class "Default")
      (node (ref "PPM") (pin "3") (pinfunction "3_3") (pintype "passive"))
      (node (ref "R17") (pin "1") (pinfunction "1_1") (pintype "passive"))
    )
    (net (code "69") (name "Net-(R2-Pad2)") (class "Default")
      (node (ref "R2") (pin "2") (pinfunction "2_2") (pintype "passive"))
      (node (ref "X3") (pin "2") (pinfunction "2_2") (pintype "passive"))
    )
    (net (code "70") (name "Net-(R15-Pad2)") (class "Default")
      (node (ref "R15") (pin "2") (pinfunction "2_2") (pintype "passive"))
      (node (ref "X3") (pin "3") (pinfunction "3_3") (pintype "passive"))
    )
    (net (code "71") (name "Net-(R20-Pad1)") (class "Default")
      (node (ref "R20") (pin "1") (pinfunction "1_1") (pintype "passive"))
      (node (ref "UART") (pin "2") (pinfunction "2_2") (pintype "passive"))
    )
    (net (code "72") (name "Net-(R21-Pad1)") (class "Default")
      (node (ref "R21") (pin "1") (pinfunction "1_1") (pintype "passive"))
      (node (ref "UART") (pin "3") (pinfunction "3_3") (pintype "passive"))
    )
    (net (code "73") (name "Net-(R22-Pad1)") (class "Default")
      (node (ref "R22") (pin "1") (pinfunction "1_1") (pintype "passive"))
      (node (ref "SPI") (pin "2") (pinfunction "2_2") (pintype "passive"))
    )
    (net (code "74") (name "Net-(R23-Pad1)") (class "Default")
      (node (ref "R23") (pin "1") (pinfunction "1_1") (pintype "passive"))
      (node (ref "SPI") (pin "3") (pinfunction "3_3") (pintype "passive"))
    )
    (net (code "75") (name "Net-(R24-Pad1)") (class "Default")
      (node (ref "R24") (pin "1") (pinfunction "1_1") (pintype "passive"))
      (node (ref "SPI") (pin "5") (pinfunction "5_5") (pintype "passive"))
    )
    (net (code "76") (name "Net-(R25-Pad1)") (class "Default")
      (node (ref "R25") (pin "1") (pinfunction "1_1") (pintype "passive"))
      (node (ref "SPI") (pin "4") (pinfunction "4_4") (pintype "passive"))
    )
    (net (code "77") (name "Net-(R30-PadSA)") (class "Default")
      (node (ref "R30") (pin "SA") (pinfunction "SA_SA") (pintype "passive"))
      (node (ref "R32") (pin "1") (pinfunction "1_1") (pintype "passive"))
    )
    (net (code "78") (name "Net-(R30-PadSB)") (class "Default")
      (node (ref "R30") (pin "SB") (pinfunction "SB_SB") (pintype "passive"))
      (node (ref "R31") (pin "1") (pinfunction "1_1") (pintype "passive"))
    )
    (net (code "79") (name "Net-(V+-1)") (class "Default")
      (node (ref "R35") (pin "2") (pinfunction "2_2") (pintype "passive"))
      (node (ref "V+") (pin "1@1") (pinfunction "1_1@1") (pintype "bidirectional"))
      (node (ref "V+") (pin "1@2") (pinfunction "2_1@2") (pintype "bidirectional"))
    )
    (net (code "80") (name "Net-(V-_OUT-1)") (class "Default")
      (node (ref "R30") (pin "A") (pinfunction "A_A") (pintype "passive"))
      (node (ref "V-_OUT") (pin "1@1") (pinfunction "1_1@1") (pintype "bidirectional"))
      (node (ref "V-_OUT") (pin "1@2") (pinfunction "2_1@2") (pintype "bidirectional"))
    )
    (net (code "81") (name "Net-(X1B-F)") (class "Default")
      (node (ref "R10") (pin "1") (pinfunction "1_1") (pintype "passive"))
      (node (ref "X1") (pin "10") (pinfunction "F_10") (pintype "passive"))
    )
    (net (code "82") (name "Net-(X1G-F)") (class "Default")
      (node (ref "R4") (pin "1") (pinfunction "1_1") (pintype "passive"))
      (node (ref "X1") (pin "15") (pinfunction "F_15") (pintype "passive"))
    )
    (net (code "83") (name "Net-(X1H-F)") (class "Default")
      (node (ref "R5") (pin "2") (pinfunction "2_2") (pintype "passive"))
      (node (ref "X1") (pin "16") (pinfunction "F_16") (pintype "passive"))
    )
    (net (code "84") (name "Net-(X1J-F)") (class "Default")
      (node (ref "R13") (pin "1") (pinfunction "1_1") (pintype "passive"))
      (node (ref "X1") (pin "18") (pinfunction "F_18") (pintype "passive"))
    )
    (net (code "85") (name "Net-(X1K-F)") (class "Default")
      (node (ref "R7") (pin "2") (pinfunction "2_2") (pintype "passive"))
      (node (ref "X1") (pin "19") (pinfunction "F_19") (pintype "passive"))
    )
    (net (code "86") (name "Net-(X1L-F)") (class "Default")
      (node (ref "R3") (pin "2") (pinfunction "2_2") (pintype "passive"))
      (node (ref "X1") (pin "2") (pinfunction "F_2") (pintype "passive"))
    )
    (net (code "87") (name "Net-(X1N-F)") (class "Default")
      (node (ref "R14") (pin "1") (pinfunction "1_1") (pintype "passive"))
      (node (ref "X1") (pin "21") (pinfunction "F_21") (pintype "passive"))
    )
    (net (code "88") (name "Net-(X1O-F)") (class "Default")
      (node (ref "R8") (pin "2") (pinfunction "2_2") (pintype "passive"))
      (node (ref "X1") (pin "22") (pinfunction "F_22") (pintype "passive"))
    )
    (net (code "89") (name "Net-(X1T-F)") (class "Default")
      (node (ref "R6") (pin "1") (pinfunction "1_1") (pintype "passive"))
      (node (ref "X1") (pin "4") (pinfunction "F_4") (pintype "passive"))
    )
    (net (code "90") (name "Net-(X1U-F)") (class "Default")
      (node (ref "R11") (pin "2") (pinfunction "2_2") (pintype "passive"))
      (node (ref "X1") (pin "5") (pinfunction "F_5") (pintype "passive"))
    )
    (net (code "91") (name "Net-(X1W-F)") (class "Default")
      (node (ref "R9") (pin "1") (pinfunction "1_1") (pintype "passive"))
      (node (ref "X1") (pin "7") (pinfunction "F_7") (pintype "passive"))
    )
    (net (code "92") (name "Net-(X1X-F)") (class "Default")
      (node (ref "R12") (pin "2") (pinfunction "2_2") (pintype "passive"))
      (node (ref "X1") (pin "8") (pinfunction "F_8") (pintype "passive"))
    )
    (net (code "93") (name "PPM") (class "Default")
      (node (ref "IC1") (pin "37") (pinfunction "PB2_37") (pintype "bidirectional"))
      (node (ref "R17") (pin "2") (pinfunction "2_2") (pintype "passive"))
    )
    (net (code "94") (name "SPI2_MISO") (class "Default")
      (node (ref "IC1") (pin "53") (pinfunction "PB14_53") (pintype "bidirectional"))
      (node (ref "R25") (pin "2") (pinfunction "2_2") (pintype "passive"))
    )
    (net (code "95") (name "SPI2_MOSI") (class "Default")
      (node (ref "IC1") (pin "54") (pinfunction "PB15_54") (pintype "bidirectional"))
      (node (ref "R23") (pin "2") (pinfunction "2_2") (pintype "passive"))
    )
    (net (code "96") (name "SPI2_NSS") (class "Default")
      (node (ref "IC1") (pin "51") (pinfunction "PB12_51") (pintype "bidirectional"))
      (node (ref "R24") (pin "2") (pinfunction "2_2") (pintype "passive"))
    )
    (net (code "97") (name "SPI2_SCK") (class "Default")
      (node (ref "IC1") (pin "52") (pinfunction "PB13_52") (pintype "bidirectional"))
      (node (ref "R22") (pin "2") (pinfunction "2_2") (pintype "passive"))
    )
    (net (code "98") (name "SWCLK") (class "Default")
      (node (ref "IC1") (pin "76") (pinfunction "PA14_76") (pintype "bidirectional"))
      (node (ref "SWD") (pin "2") (pinfunction "2_2") (pintype "passive"))
    )
    (net (code "99") (name "SWDIO") (class "Default")
      (node (ref "IC1") (pin "72") (pinfunction "PA13_72") (pintype "bidirectional"))
      (node (ref "SWD") (pin "4") (pinfunction "4_4") (pintype "passive"))
    )
    (net (code "100") (name "USB+") (class "Default")
      (node (ref "IC1") (pin "71") (pinfunction "PA12_71") (pintype "bidirectional"))
      (node (ref "R15") (pin "1") (pinfunction "1_1") (pintype "passive"))
    )
    (net (code "101") (name "USB-") (class "Default")
      (node (ref "IC1") (pin "70") (pinfunction "PA11_70") (pintype "bidirectional"))
      (node (ref "R2") (pin "1") (pinfunction "1_1") (pintype "passive"))
    )
    (net (code "102") (name "unconnected-(DISPLAY1C-CS-Pad29)") (class "Default")
      (node (ref "DISPLAY1") (pin "29") (pinfunction "CS_29") (pintype "bidirectional"))
    )
    (net (code "103") (name "unconnected-(DISPLAY1C-RST-Pad33)") (class "Default")
      (node (ref "DISPLAY1") (pin "33") (pinfunction "RST_33") (pintype "bidirectional"))
    )
    (net (code "104") (name "unconnected-(IC1A-NRST-Pad14)") (class "Default")
      (node (ref "IC1") (pin "14") (pinfunction "NRST_14") (pintype "bidirectional"))
    )
    (net (code "105") (name "unconnected-(IC1A-OSC_IN-Pad12)") (class "Default")
      (node (ref "IC1") (pin "12") (pinfunction "OSC_IN_12") (pintype "bidirectional"))
    )
    (net (code "106") (name "unconnected-(IC1A-OSC_OUT-Pad13)") (class "Default")
      (node (ref "IC1") (pin "13") (pinfunction "OSC_OUT_13") (pintype "bidirectional"))
    )
    (net (code "107") (name "unconnected-(IC1A-PA0-WKUP-Pad23)") (class "Default")
      (node (ref "IC1") (pin "23") (pinfunction "PA0-WKUP_23") (pintype "bidirectional"))
    )
    (net (code "108") (name "unconnected-(IC1A-PA1-Pad24)") (class "Default")
      (node (ref "IC1") (pin "24") (pinfunction "PA1_24") (pintype "bidirectional"))
    )
    (net (code "109") (name "unconnected-(IC1A-PA4-Pad29)") (class "Default")
      (node (ref "IC1") (pin "29") (pinfunction "PA4_29") (pintype "bidirectional"))
    )
    (net (code "110") (name "unconnected-(IC1A-PA8-Pad67)") (class "Default")
      (node (ref "IC1") (pin "67") (pinfunction "PA8_67") (pintype "bidirectional"))
    )
    (net (code "111") (name "unconnected-(IC1A-PA10-Pad69)") (class "Default")
      (node (ref "IC1") (pin "69") (pinfunction "PA10_69") (pintype "bidirectional"))
    )
    (net (code "112") (name "unconnected-(IC1A-PA15-Pad77)") (class "Default")
      (node (ref "IC1") (pin "77") (pinfunction "PA15_77") (pintype "bidirectional"))
    )
    (net (code "113") (name "unconnected-(IC1A-PB3-Pad89)") (class "Default")
      (node (ref "IC1") (pin "89") (pinfunction "PB3_89") (pintype "bidirectional"))
    )
    (net (code "114") (name "unconnected-(IC1A-PB4-Pad90)") (class "Default")
      (node (ref "IC1") (pin "90") (pinfunction "PB4_90") (pintype "bidirectional"))
    )
    (net (code "115") (name "unconnected-(IC1A-PB5-Pad91)") (class "Default")
      (node (ref "IC1") (pin "91") (pinfunction "PB5_91") (pintype "bidirectional"))
    )
    (net (code "116") (name "unconnected-(IC1A-PB6-Pad92)") (class "Default")
      (node (ref "IC1") (pin "92") (pinfunction "PB6_92") (pintype "bidirectional"))
    )
    (net (code "117") (name "unconnected-(IC1A-PB7-Pad93)") (class "Default")
      (node (ref "IC1") (pin "93") (pinfunction "PB7_93") (pintype "bidirectional"))
    )
    (net (code "118") (name "unconnected-(IC1A-PC2-Pad17)") (class "Default")
      (node (ref "IC1") (pin "17") (pinfunction "PC2_17") (pintype "bidirectional"))
    )
    (net (code "119") (name "unconnected-(IC1A-PC3-Pad18)") (class "Default")
      (node (ref "IC1") (pin "18") (pinfunction "PC3_18") (pintype "bidirectional"))
    )
    (net (code "120") (name "unconnected-(IC1A-PC13-Pad7)") (class "Default")
      (node (ref "IC1") (pin "7") (pinfunction "PC13_7") (pintype "bidirectional"))
    )
    (net (code "121") (name "unconnected-(IC1A-PC14-Pad8)") (class "Default")
      (node (ref "IC1") (pin "8") (pinfunction "PC14_8") (pintype "bidirectional"))
    )
    (net (code "122") (name "unconnected-(IC1A-PC15-Pad9)") (class "Default")
      (node (ref "IC1") (pin "9") (pinfunction "PC15_9") (pintype "bidirectional"))
    )
    (net (code "123") (name "unconnected-(IC1A-PE0-Pad97)") (class "Default")
      (node (ref "IC1") (pin "97") (pinfunction "PE0_97") (pintype "bidirectional"))
    )
    (net (code "124") (name "unconnected-(IC1A-PE1-Pad98)") (class "Default")
      (node (ref "IC1") (pin "98") (pinfunction "PE1_98") (pintype "bidirectional"))
    )
    (net (code "125") (name "unconnected-(IC1A-PE2-Pad1)") (class "Default")
      (node (ref "IC1") (pin "1") (pinfunction "PE2_1") (pintype "bidirectional"))
    )
    (net (code "126") (name "unconnected-(IC1A-PE3-Pad2)") (class "Default")
      (node (ref "IC1") (pin "2") (pinfunction "PE3_2") (pintype "bidirectional"))
    )
    (net (code "127") (name "unconnected-(IC1A-PE4-Pad3)") (class "Default")
      (node (ref "IC1") (pin "3") (pinfunction "PE4_3") (pintype "bidirectional"))
    )
    (net (code "128") (name "unconnected-(IC1A-PE5-Pad4)") (class "Default")
      (node (ref "IC1") (pin "4") (pinfunction "PE5_4") (pintype "bidirectional"))
    )
    (net (code "129") (name "unconnected-(IC1A-PE6-Pad5)") (class "Default")
      (node (ref "IC1") (pin "5") (pinfunction "PE6_5") (pintype "bidirectional"))
    )
    (net (code "130") (name "unconnected-(IC1A-PE7-Pad38)") (class "Default")
      (node (ref "IC1") (pin "38") (pinfunction "PE7_38") (pintype "bidirectional"))
    )
    (net (code "131") (name "unconnected-(IC1A-PE8-Pad39)") (class "Default")
      (node (ref "IC1") (pin "39") (pinfunction "PE8_39") (pintype "bidirectional"))
    )
    (net (code "132") (name "unconnected-(IC1A-PE9-Pad40)") (class "Default")
      (node (ref "IC1") (pin "40") (pinfunction "PE9_40") (pintype "bidirectional"))
    )
    (net (code "133") (name "unconnected-(IC1A-PE10-Pad41)") (class "Default")
      (node (ref "IC1") (pin "41") (pinfunction "PE10_41") (pintype "bidirectional"))
    )
    (net (code "134") (name "unconnected-(IC1A-PE11-Pad42)") (class "Default")
      (node (ref "IC1") (pin "42") (pinfunction "PE11_42") (pintype "bidirectional"))
    )
    (net (code "135") (name "unconnected-(IC1A-PE12-Pad43)") (class "Default")
      (node (ref "IC1") (pin "43") (pinfunction "PE12_43") (pintype "bidirectional"))
    )
    (net (code "136") (name "unconnected-(IC1A-PE13-Pad44)") (class "Default")
      (node (ref "IC1") (pin "44") (pinfunction "PE13_44") (pintype "bidirectional"))
    )
    (net (code "137") (name "unconnected-(IC1A-PE14-Pad45)") (class "Default")
      (node (ref "IC1") (pin "45") (pinfunction "PE14_45") (pintype "bidirectional"))
    )
    (net (code "138") (name "unconnected-(IC1A-PE15-Pad46)") (class "Default")
      (node (ref "IC1") (pin "46") (pinfunction "PE15_46") (pintype "bidirectional"))
    )
    (net (code "139") (name "unconnected-(IC2-GPIO0{slash}CLK-Pad23)") (class "Default")
      (node (ref "IC2") (pin "23") (pinfunction "GPIO0/CLK_23") (pintype "bidirectional"))
    )
    (net (code "140") (name "unconnected-(IC2-GPIO1{slash}SYNC-Pad25)") (class "Default")
      (node (ref "IC2") (pin "25") (pinfunction "GPIO1/SYNC_25") (pintype "bidirectional"))
    )
    (net (code "141") (name "unconnected-(IC2-GPO0-Pad24)") (class "Default")
      (node (ref "IC2") (pin "24") (pinfunction "GPO0_24") (pintype "bidirectional"))
    )
    (net (code "142") (name "unconnected-(IC2-GPO1-Pad22)") (class "Default")
      (node (ref "IC2") (pin "22") (pinfunction "GPO1_22") (pintype "bidirectional"))
    )
  )
)
